# sensor_module.net
KiCad netlist of a schematic drawn in Altium Designer
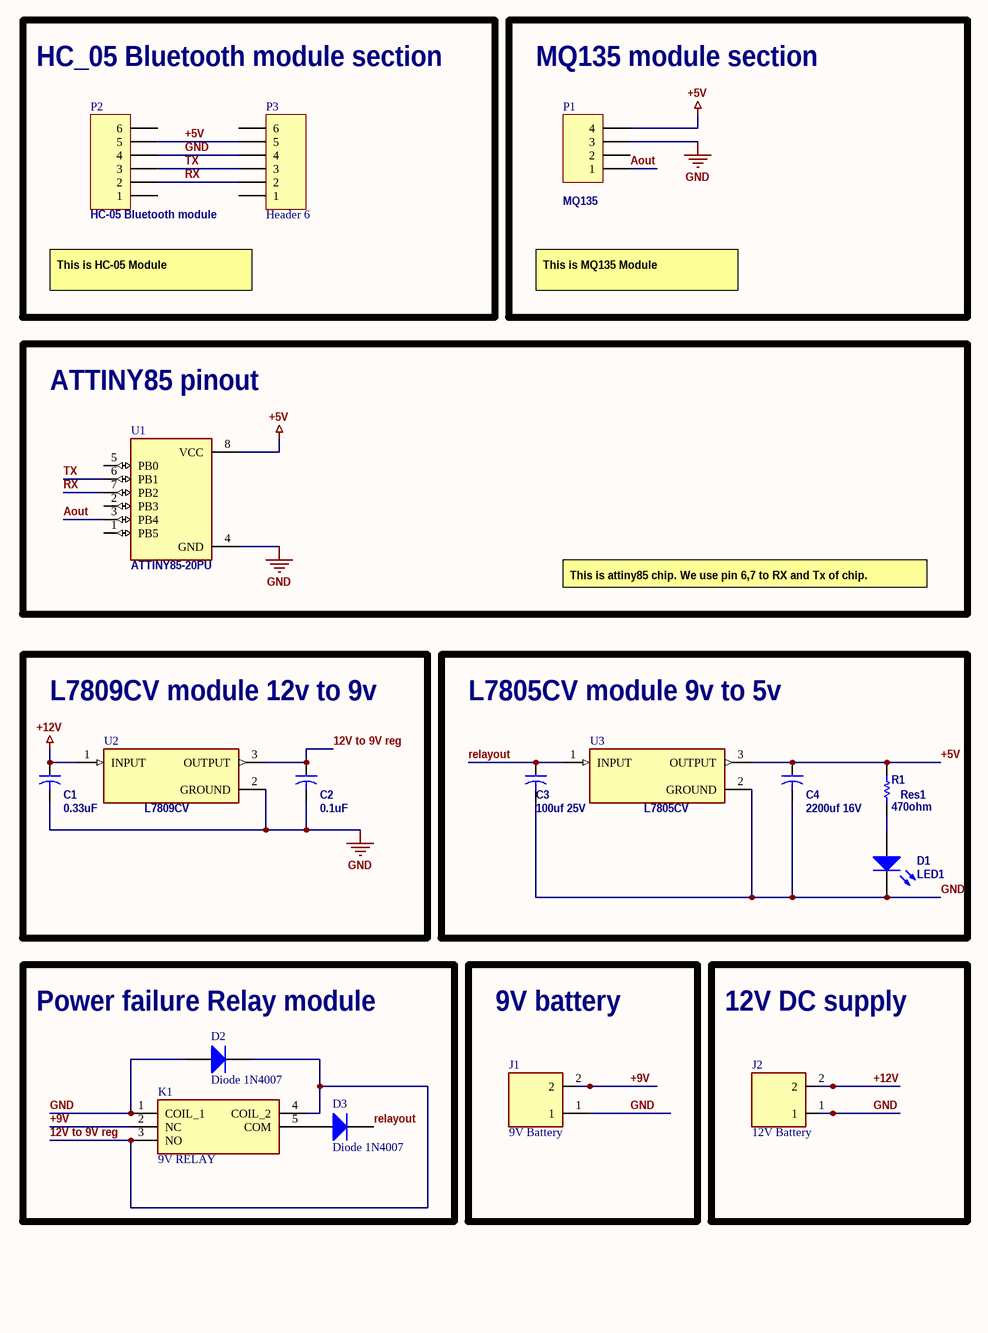
[diagram p0: sensor module.SchDoc]

(export (version "E")
  (design (tool "Eeschema 10.0.6"))
  (components
    (comp (ref "C1")
      (value "0.33uF")
      (footprint "CAPR5-4X5")
      (description "Capacitor")
      (fields (field (name "PUBLISHER") "Altium Limited"))
      (libsource (lib "Miscellaneous Devices") (part "Cap2"))
    )
    (comp (ref "C2")
      (value "0.1uF")
      (footprint "CAPR5-4X5")
      (description "Capacitor")
      (fields (field (name "PUBLISHER") "Altium Limited"))
      (libsource (lib "Miscellaneous Devices") (part "Cap2"))
    )
    (comp (ref "C3")
      (value "100uf 25V")
      (footprint "CAPR5-4X5")
      (description "Capacitor")
      (fields (field (name "PUBLISHER") "Altium Limited"))
      (libsource (lib "Miscellaneous Devices") (part "Cap2"))
    )
    (comp (ref "C4")
      (value "2200uf 16V")
      (footprint "CAPR5-4X5")
      (description "Capacitor")
      (fields (field (name "PUBLISHER") "Altium Limited"))
      (libsource (lib "Miscellaneous Devices") (part "Cap2"))
    )
    (comp (ref "D1")
      (value "LED1")
      (footprint "LED-1")
      (description "Typical RED GaAs LED")
      (fields (field (name "PUBLISHER") "Altium Limited"))
      (libsource (lib "Miscellaneous Devices") (part "LED1"))
    )
    (comp (ref "D2")
      (value "Diode 1N4007")
      (footprint "DO-41")
      (description "1 Amp General Purpose Rectifier")
      (fields (field (name "PUBLISHER") "Altium Limited"))
      (libsource (lib "Miscellaneous Devices") (part "Diode 1N4007"))
    )
    (comp (ref "D3")
      (value "Diode 1N4007")
      (footprint "DO-41")
      (description "1 Amp General Purpose Rectifier")
      (fields (field (name "PUBLISHER") "Altium Limited"))
      (libsource (lib "Miscellaneous Devices") (part "Diode 1N4007"))
    )
    (comp (ref "J1")
      (value "9V Battery")
      (footprint "HANDSON_KF301-2P")
      (description "2 Pin Terminal Block 5mm Pitch")
      (fields (field (name "MP") "KF301-2P"))
      (libsource (lib "KF301-2P") (part "KF301-2P"))
    )
    (comp (ref "J2")
      (value "12V Battery")
      (footprint "HANDSON_KF301-2P")
      (description "2 Pin Terminal Block 5mm Pitch")
      (fields (field (name "MP") "KF301-2P"))
      (libsource (lib "KF301-2P") (part "KF301-2P"))
    )
    (comp (ref "K1")
      (value "9V RELAY")
      (footprint "JQC3FT731Z12VDC")
      (description "RELAY POWER 10A 12VDC 1C PCB TYPE (JS1) 5PIN QIANJ")
      (fields (field (name "MANUFACTURER_PART_NUMBER") "JQC-3F-(T73)-1Z-12VDC"))
      (libsource (lib "LIB_JQC-3F-_T73_-1Z-9VDC") (part "JQC-3F-_T73_-1Z-12VDC"))
    )
    (comp (ref "P1")
      (value "MQ135")
      (footprint "HDR1X4")
      (description "Header, 4-Pin")
      (fields (field (name "PUBLISHER") "Altium Limited"))
      (libsource (lib "Miscellaneous Connectors") (part "Header 4"))
    )
    (comp (ref "P2")
      (value "HC-05 Bluetooth module")
      (footprint "HDR1X6")
      (description "Header, 6-Pin")
      (fields (field (name "PUBLISHER") "Altium Limited"))
      (libsource (lib "") (part "Header 6_1"))
    )
    (comp (ref "P3")
      (value "Header 6")
      (footprint "HDR1X6")
      (description "Header, 6-Pin")
      (fields (field (name "PUBLISHER") "Altium Limited"))
      (libsource (lib "Miscellaneous Connectors") (part "Header 6"))
    )
    (comp (ref "R1")
      (value "Res1")
      (footprint "AXIAL-0.3")
      (description "Resistor")
      (fields (field (name "ALTIUM_VALUE") "470ohm") (field (name "PUBLISHER") "Altium Limited"))
      (libsource (lib "Miscellaneous Devices") (part "Res1"))
    )
    (comp (ref "U1")
      (value "ATTINY85-20PU")
      (footprint "DIP762W46P254L927H533Q8B")
      (fields (field (name "MF") "Microchip"))
      (libsource (lib "ATTINY85-20PU") (part "ATTINY85-20PU"))
    )
    (comp (ref "U2")
      (value "L7809CV")
      (footprint "TO255P1040X460X1968-3")
      (description "Linear Voltage Regulator IC Positive Fixed 1 Output 1.5A TO-220")
      (fields (field (name "MP") "L7805CV") (field (name "MF") "STMicroelectronics"))
      (libsource (lib "L7805CV") (part "L7805CV"))
    )
    (comp (ref "U3")
      (value "L7805CV")
      (footprint "TO255P1040X460X1968-3")
      (description "Linear Voltage Regulator IC Positive Fixed 1 Output 1.5A TO-220")
      (fields (field (name "MF") "STMicroelectronics"))
      (libsource (lib "L7805CV") (part "L7805CV"))
    )
  )
  (nets
    (net (code "1") (name "+5V") (class "Default")
      (node (ref "C4") (pin "1") (pinfunction "1_1") (pintype "passive"))
      (node (ref "P1") (pin "4") (pinfunction "4_4") (pintype "passive"))
      (node (ref "P2") (pin "5") (pinfunction "5_5") (pintype "passive"))
      (node (ref "P3") (pin "5") (pinfunction "5_5") (pintype "passive"))
      (node (ref "R1") (pin "2") (pinfunction "2_2") (pintype "passive"))
      (node (ref "U1") (pin "8") (pinfunction "VCC_8") (pintype "power_in"))
      (node (ref "U3") (pin "3") (pinfunction "OUTPUT_3") (pintype "output"))
    )
    (net (code "2") (name "+12V") (class "Default")
      (node (ref "C1") (pin "1") (pinfunction "1_1") (pintype "passive"))
      (node (ref "J2") (pin "2") (pinfunction "2_2") (pintype "passive"))
      (node (ref "U2") (pin "1") (pinfunction "INPUT_1") (pintype "input"))
    )
    (net (code "3") (name "/+9V") (class "Default")
      (node (ref "J1") (pin "2") (pinfunction "2_2") (pintype "passive"))
      (node (ref "K1") (pin "2") (pinfunction "NC_2") (pintype "passive"))
    )
    (net (code "4") (name "/12V to 9V reg") (class "Default")
      (node (ref "C2") (pin "1") (pinfunction "1_1") (pintype "passive"))
      (node (ref "D2") (pin "2") (pinfunction "K_2") (pintype "passive"))
      (node (ref "K1") (pin "3") (pinfunction "NO_3") (pintype "passive"))
      (node (ref "K1") (pin "4") (pinfunction "COIL_2_4") (pintype "passive"))
      (node (ref "U2") (pin "3") (pinfunction "OUTPUT_3") (pintype "output"))
    )
    (net (code "5") (name "/Aout") (class "Default")
      (node (ref "P1") (pin "1") (pinfunction "1_1") (pintype "passive"))
      (node (ref "U1") (pin "3") (pinfunction "PB4_3") (pintype "bidirectional"))
    )
    (net (code "6") (name "/RX") (class "Default")
      (node (ref "P2") (pin "2") (pinfunction "2_2") (pintype "passive"))
      (node (ref "P3") (pin "2") (pinfunction "2_2") (pintype "passive"))
      (node (ref "U1") (pin "7") (pinfunction "PB2_7") (pintype "bidirectional"))
    )
    (net (code "7") (name "/TX") (class "Default")
      (node (ref "P2") (pin "3") (pinfunction "3_3") (pintype "passive"))
      (node (ref "P3") (pin "3") (pinfunction "3_3") (pintype "passive"))
      (node (ref "U1") (pin "6") (pinfunction "PB1_6") (pintype "bidirectional"))
    )
    (net (code "8") (name "/relayout") (class "Default")
      (node (ref "C3") (pin "1") (pinfunction "1_1") (pintype "passive"))
      (node (ref "D3") (pin "2") (pinfunction "K_2") (pintype "passive"))
      (node (ref "U3") (pin "1") (pinfunction "INPUT_1") (pintype "input"))
    )
    (net (code "9") (name "GND") (class "Default")
      (node (ref "C1") (pin "2") (pinfunction "2_2") (pintype "passive"))
      (node (ref "C2") (pin "2") (pinfunction "2_2") (pintype "passive"))
      (node (ref "C3") (pin "2") (pinfunction "2_2") (pintype "passive"))
      (node (ref "C4") (pin "2") (pinfunction "2_2") (pintype "passive"))
      (node (ref "D1") (pin "2") (pinfunction "K_2") (pintype "passive"))
      (node (ref "D2") (pin "1") (pinfunction "A_1") (pintype "passive"))
      (node (ref "J1") (pin "1") (pinfunction "1_1") (pintype "passive"))
      (node (ref "J2") (pin "1") (pinfunction "1_1") (pintype "passive"))
      (node (ref "K1") (pin "1") (pinfunction "COIL_1_1") (pintype "passive"))
      (node (ref "P1") (pin "3") (pinfunction "3_3") (pintype "passive"))
      (node (ref "P2") (pin "4") (pinfunction "4_4") (pintype "passive"))
      (node (ref "P3") (pin "4") (pinfunction "4_4") (pintype "passive"))
      (node (ref "U1") (pin "4") (pinfunction "GND_4") (pintype "power_in"))
      (node (ref "U2") (pin "2") (pinfunction "GROUND_2") (pintype "power_in"))
      (node (ref "U3") (pin "2") (pinfunction "GROUND_2") (pintype "power_in"))
    )
    (net (code "10") (name "Net-(D1-A)") (class "Default")
      (node (ref "D1") (pin "1") (pinfunction "A_1") (pintype "passive"))
      (node (ref "R1") (pin "1") (pinfunction "1_1") (pintype "passive"))
    )
    (net (code "11") (name "Net-(D3-A)") (class "Default")
      (node (ref "D3") (pin "1") (pinfunction "A_1") (pintype "passive"))
      (node (ref "K1") (pin "5") (pinfunction "COM_5") (pintype "passive"))
    )
    (net (code "12") (name "unconnected-(P1-Pad2)") (class "Default")
      (node (ref "P1") (pin "2") (pinfunction "2_2") (pintype "passive"))
    )
    (net (code "13") (name "unconnected-(P2-Pad1)") (class "Default")
      (node (ref "P2") (pin "1") (pinfunction "1_1") (pintype "passive"))
    )
    (net (code "14") (name "unconnected-(P2-Pad6)") (class "Default")
      (node (ref "P2") (pin "6") (pinfunction "6_6") (pintype "passive"))
    )
    (net (code "15") (name "unconnected-(P3-Pad1)") (class "Default")
      (node (ref "P3") (pin "1") (pinfunction "1_1") (pintype "passive"))
    )
    (net (code "16") (name "unconnected-(P3-Pad6)") (class "Default")
      (node (ref "P3") (pin "6") (pinfunction "6_6") (pintype "passive"))
    )
    (net (code "17") (name "unconnected-(U1-PB0-Pad5)") (class "Default")
      (node (ref "U1") (pin "5") (pinfunction "PB0_5") (pintype "bidirectional"))
    )
    (net (code "18") (name "unconnected-(U1-PB3-Pad2)") (class "Default")
      (node (ref "U1") (pin "2") (pinfunction "PB3_2") (pintype "bidirectional"))
    )
    (net (code "19") (name "unconnected-(U1-PB5-Pad1)") (class "Default")
      (node (ref "U1") (pin "1") (pinfunction "PB5_1") (pintype "bidirectional"))
    )
  )
)
